# Level_Switch_by_9013.net
KiCad netlist of a schematic drawn in Altium Designer
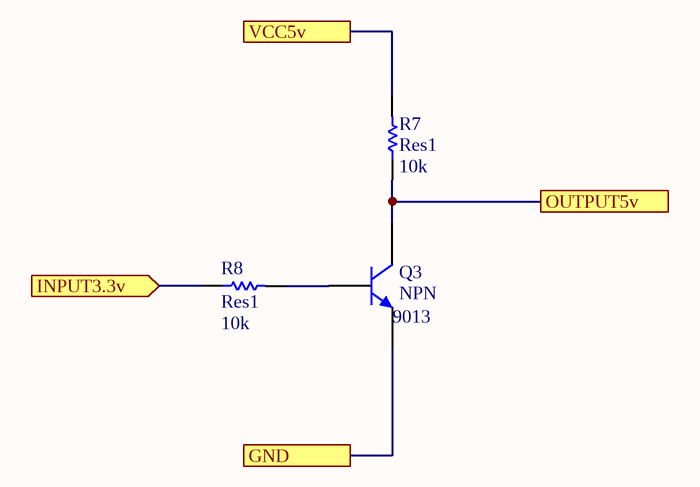
[diagram p0: Level_Switch_by_9013.SchDoc]

(export (version "E")
  (design (tool "Eeschema 10.0.6"))
  (components
    (comp (ref "Q3")
      (value "NPN")
      (footprint "SOT-23")
      (description "NPN Bipolar Transistor")
      (fields (field (name "NAME") "9013") (field (name "PUBLISHER") "Altium Limited"))
      (libsource (lib "Integrated_Library") (part "NPN"))
    )
    (comp (ref "R7")
      (value "Res1")
      (footprint "R0805")
      (description "Resistor")
      (fields (field (name "ALTIUM_VALUE") "10k"))
      (libsource (lib "Integrated_Library") (part "Res1"))
    )
    (comp (ref "R8")
      (value "Res1")
      (footprint "R0805")
      (description "Resistor")
      (fields (field (name "ALTIUM_VALUE") "10k"))
      (libsource (lib "Integrated_Library") (part "Res1"))
    )
  )
  (nets
    (net (code "1") (name "/GND") (class "Default")
      (node (ref "Q3") (pin "3") (pinfunction "E_3") (pintype "passive"))
    )
    (net (code "2") (name "/INPUT3.3v") (class "Default")
      (node (ref "R8") (pin "1") (pinfunction "1_1") (pintype "passive"))
    )
    (net (code "3") (name "/OUTPUT5v") (class "Default")
      (node (ref "Q3") (pin "1") (pinfunction "C_1") (pintype "passive"))
      (node (ref "R7") (pin "1") (pinfunction "1_1") (pintype "passive"))
    )
    (net (code "4") (name "/VCC5v") (class "Default")
      (node (ref "R7") (pin "2") (pinfunction "2_2") (pintype "passive"))
    )
    (net (code "5") (name "Net-(Q3-B)") (class "Default")
      (node (ref "Q3") (pin "2") (pinfunction "B_2") (pintype "passive"))
      (node (ref "R8") (pin "2") (pinfunction "2_2") (pintype "passive"))
    )
  )
)
